# CH32V203CCT-R0.net
KiCad netlist of a schematic drawn in Altium Designer
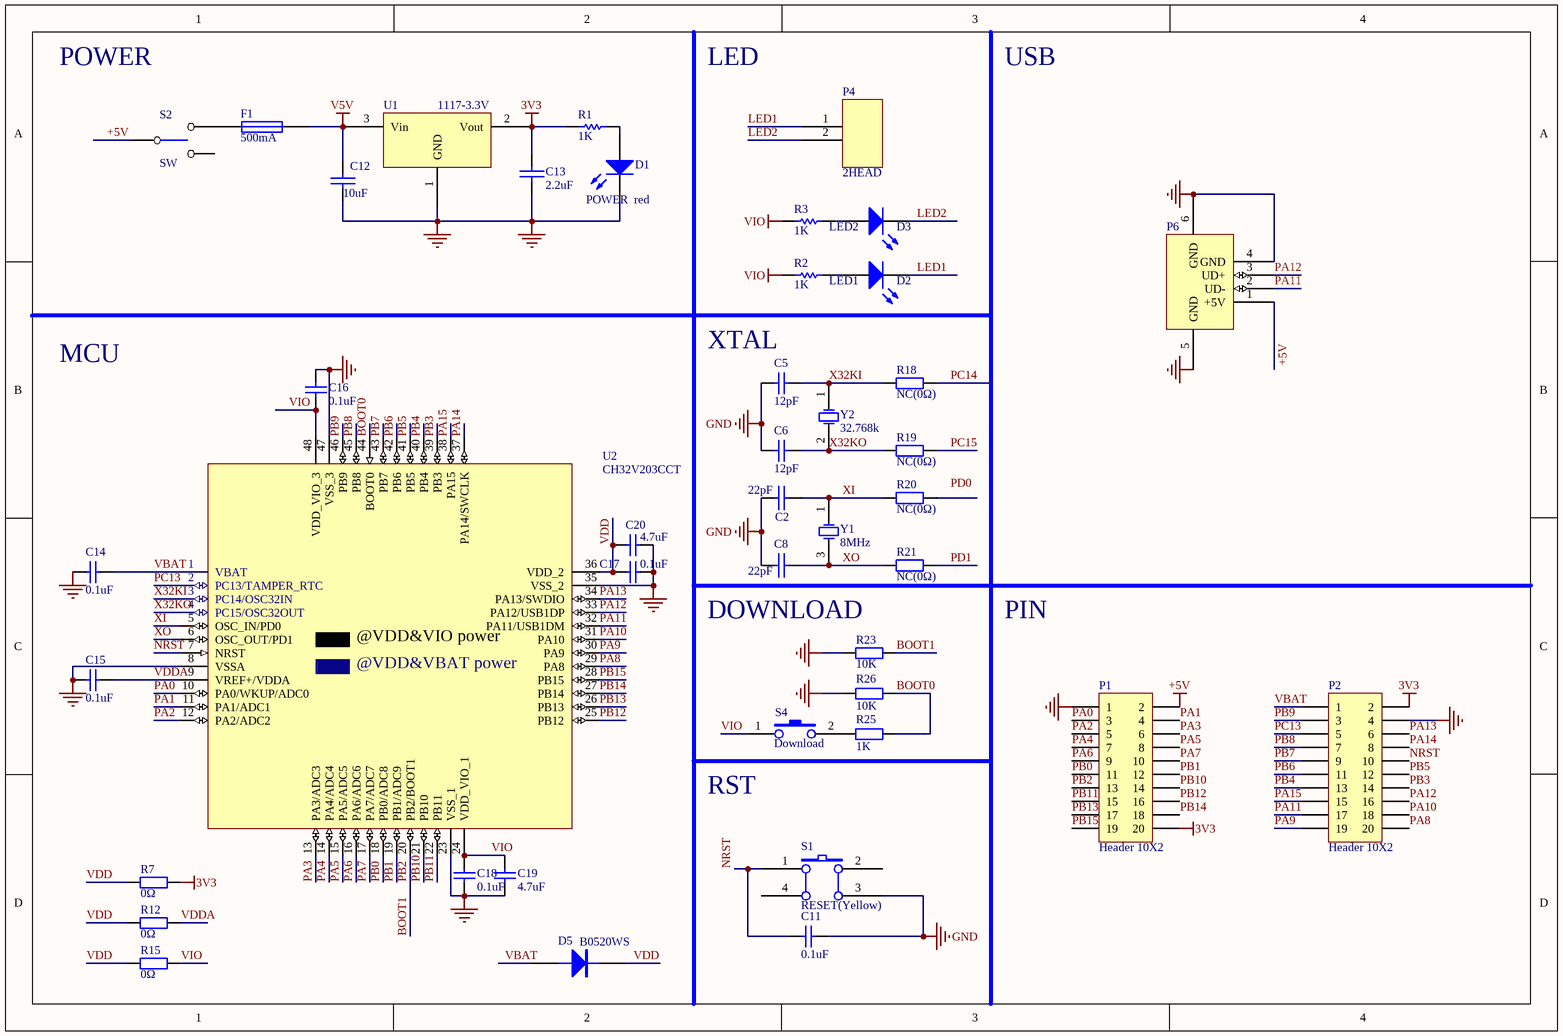
[diagram p0: CH32V203CCT-R0.SchDoc]

(export (version "E")
  (design (tool "Eeschema 10.0.6"))
  (components
    (comp (ref "C2")
      (value "22pF")
      (footprint "0603_C")
      (description "Capacitor")
      (libsource (lib "*") (part "CAP"))
    )
    (comp (ref "C5")
      (value "12pF")
      (footprint "0603_C")
      (description "Capacitor")
      (libsource (lib "Miscellaneous Devices") (part "Cap"))
    )
    (comp (ref "C6")
      (value "12pF")
      (footprint "0603_C")
      (description "Capacitor")
      (libsource (lib "Miscellaneous Devices") (part "Cap"))
    )
    (comp (ref "C8")
      (value "22pF")
      (footprint "0603_C")
      (description "Capacitor")
      (libsource (lib "*") (part "CAP"))
    )
    (comp (ref "C11")
      (value "0.1uF")
      (footprint "0603_C")
      (description "Capacitor")
      (libsource (lib "Miscellaneous Devices") (part "Cap"))
    )
    (comp (ref "C12")
      (value "10uF")
      (footprint "3216_C")
      (description "Capacitor")
      (libsource (lib "*") (part "CAP"))
    )
    (comp (ref "C13")
      (value "2.2uF")
      (footprint "0603_C")
      (description "Capacitor")
      (libsource (lib "*") (part "CAP"))
    )
    (comp (ref "C14")
      (value "0.1uF")
      (footprint "0603_C")
      (description "Capacitor")
      (fields (field (name "PUBLISHER") "Altium Limited"))
      (libsource (lib "*") (part "Cap"))
    )
    (comp (ref "C15")
      (value "0.1uF")
      (footprint "0603_C")
      (description "Capacitor")
      (fields (field (name "PUBLISHER") "Altium Limited"))
      (libsource (lib "*") (part "Cap"))
    )
    (comp (ref "C16")
      (value "0.1uF")
      (footprint "0603_C")
      (description "Capacitor")
      (fields (field (name "PUBLISHER") "Altium Limited"))
      (libsource (lib "*") (part "Cap"))
    )
    (comp (ref "C17")
      (value "0.1uF")
      (footprint "0603_C")
      (description "Capacitor")
      (fields (field (name "PUBLISHER") "Altium Limited"))
      (libsource (lib "*") (part "Cap"))
    )
    (comp (ref "C18")
      (value "0.1uF")
      (footprint "0603_C")
      (description "Capacitor")
      (fields (field (name "PUBLISHER") "Altium Limited"))
      (libsource (lib "*") (part "Cap"))
    )
    (comp (ref "C19")
      (value "4.7uF")
      (footprint "0603_C")
      (description "Capacitor")
      (fields (field (name "PUBLISHER") "Altium Limited"))
      (libsource (lib "*") (part "Cap"))
    )
    (comp (ref "C20")
      (value "4.7uF")
      (footprint "0603_C")
      (description "Capacitor")
      (fields (field (name "PUBLISHER") "Altium Limited"))
      (libsource (lib "*") (part "Cap"))
    )
    (comp (ref "D1")
      (value "POWER  red")
      (footprint "0603+")
      (description "Typical INFRARED GaAs LED")
      (fields (field (name "PUBLISHER") "Altium Limited"))
      (libsource (lib "*") (part "LED0"))
    )
    (comp (ref "D2")
      (value "LED1")
      (footprint "0603+")
      (description "Typical INFRARED GaAs LED")
      (fields (field (name "PUBLISHER") "Altium Limited"))
      (libsource (lib "*") (part "LED0"))
    )
    (comp (ref "D3")
      (value "LED2")
      (footprint "0603+")
      (description "Typical INFRARED GaAs LED")
      (fields (field (name "PUBLISHER") "Altium Limited"))
      (libsource (lib "*") (part "LED0"))
    )
    (comp (ref "D5")
      (value "B0520WS")
      (footprint "SOD-323")
      (description "Diode")
      (libsource (lib "*") (part "DIODE"))
    )
    (comp (ref "F1")
      (value "500mA")
      (footprint "0603")
      (description "Fuse")
      (libsource (lib "*") (part "FUSE1"))
    )
    (comp (ref "P1")
      (value "Header 10X2")
      (footprint "IDC20-2.54mm")
      (description "Header, 10-Pin, Dual row")
      (fields (field (name "PUBLISHER") "Altium Limited"))
      (libsource (lib "*") (part "Header 10X2"))
    )
    (comp (ref "P2")
      (value "Header 10X2")
      (footprint "IDC20-2.54mm")
      (description "Header, 10-Pin, Dual row")
      (fields (field (name "PUBLISHER") "Altium Limited"))
      (libsource (lib "*") (part "Header 10X2"))
    )
    (comp (ref "P4") (value "2HEAD") (footprint "SIP2-2.54mm") (libsource (lib "*") (part "2HEAD")))
    (comp (ref "P6")
      (value "USB_A")
      (footprint "USBAF")
      (description "USB Port")
      (libsource (lib "*") (part "USB"))
    )
    (comp (ref "R1")
      (value "1K")
      (footprint "0603")
      (description "Semiconductor Resistor")
      (fields (field (name "PUBLISHER") "Altium Limited"))
      (libsource (lib "*") (part "Res Semi"))
    )
    (comp (ref "R2")
      (value "1K")
      (footprint "0603")
      (description "Semiconductor Resistor")
      (fields (field (name "PUBLISHER") "Altium Limited"))
      (libsource (lib "*") (part "Res Semi"))
    )
    (comp (ref "R3")
      (value "1K")
      (footprint "0603")
      (description "Semiconductor Resistor")
      (fields (field (name "PUBLISHER") "Altium Limited"))
      (libsource (lib "*") (part "Res Semi"))
    )
    (comp (ref "R7")
      (value "0Ω")
      (footprint "0603")
      (description "Resistor")
      (libsource (lib "Miscellaneous Devices") (part "Res2"))
    )
    (comp (ref "R12")
      (value "0Ω")
      (footprint "0603")
      (description "Resistor")
      (libsource (lib "Miscellaneous Devices") (part "Res2"))
    )
    (comp (ref "R15")
      (value "0Ω")
      (footprint "0603")
      (description "Resistor")
      (libsource (lib "Miscellaneous Devices") (part "Res2"))
    )
    (comp (ref "R18")
      (value "NC(0Ω)")
      (footprint "0603")
      (description "Resistor")
      (libsource (lib "") (part "Res2_1"))
    )
    (comp (ref "R19")
      (value "NC(0Ω)")
      (footprint "0603")
      (description "Resistor")
      (libsource (lib "Miscellaneous Devices") (part "Res2"))
    )
    (comp (ref "R20")
      (value "NC(0Ω)")
      (footprint "0603")
      (description "Resistor")
      (libsource (lib "Miscellaneous Devices") (part "Res2"))
    )
    (comp (ref "R21")
      (value "NC(0Ω)")
      (footprint "0603")
      (description "Resistor")
      (libsource (lib "Miscellaneous Devices") (part "Res2"))
    )
    (comp (ref "R23")
      (value "10K")
      (footprint "CHXXX:0603")
      (description "Resistor")
      (fields (field (name "PUBLISHER") "Altium Limited"))
      (libsource (lib "Miscellaneous Devices") (part "Res2"))
    )
    (comp (ref "R25")
      (value "1K")
      (footprint "CHXXX:0603")
      (description "Resistor")
      (fields (field (name "PUBLISHER") "Altium Limited"))
      (libsource (lib "Miscellaneous Devices") (part "Res2"))
    )
    (comp (ref "R26")
      (value "10K")
      (footprint "CHXXX:0603")
      (description "Resistor")
      (fields (field (name "PUBLISHER") "Altium Limited"))
      (libsource (lib "Miscellaneous Devices") (part "Res2"))
    )
    (comp (ref "S1")
      (value "RESET(Yellow)")
      (footprint "KEYX")
      (description "SE PUSHBUTTON")
      (libsource (lib "Documents") (part "SW PUSHBUTTON"))
    )
    (comp (ref "S2") (value "SW") (footprint "KEY2") (libsource (lib "*") (part "SW")))
    (comp (ref "S4")
      (value "Download")
      (footprint "SMD_6.1x3.65x2.5mm-KEY")
      (libsource (lib "wch_sch_others") (part "KEY1"))
    )
    (comp (ref "U1")
      (value "1117-3.3V")
      (footprint "SOT-23")
      (libsource (lib "wch_sch_others") (part "6219P33M"))
    )
    (comp (ref "U2")
      (value "CH32V203CCT")
      (footprint "LQFP48")
      (description "RISC-V MCU, 192MHz, USB FS, PIOC, ADC, TKEY, 2*OPA, 2*CMP")
      (libsource (lib "CHXXX") (part "CH32V203CCT"))
    )
    (comp (ref "Y1")
      (value "8MHz")
      (footprint "XT3225")
      (description "Crystal Oscillator")
      (fields (field (name "PUBLISHER") "Altium Limited"))
      (libsource (lib "*") (part "XTAL"))
    )
    (comp (ref "Y2")
      (value "32.768k")
      (footprint "FC-135")
      (description "Crystal Oscillator")
      (fields (field (name "PUBLISHER") "Altium Limited"))
      (libsource (lib "Miscellaneous Devices") (part "XTAL"))
    )
  )
  (nets
    (net (code "1") (name "+5V") (class "Default")
      (node (ref "P1") (pin "2") (pinfunction "2_2") (pintype "passive"))
      (node (ref "P6") (pin "1") (pinfunction "+5V_1") (pintype "power_in"))
      (node (ref "S2") (pin "1") (pinfunction "1_1") (pintype "passive"))
    )
    (net (code "3") (name "/BOOT0") (class "Default")
      (node (ref "R25") (pin "1") (pinfunction "1_1") (pintype "passive"))
      (node (ref "R26") (pin "1") (pinfunction "1_1") (pintype "passive"))
      (node (ref "U2") (pin "44") (pinfunction "BOOT0_44") (pintype "input"))
    )
    (net (code "4") (name "/BOOT1") (class "Default")
      (node (ref "P1") (pin "13") (pinfunction "13_13") (pintype "passive"))
      (node (ref "R23") (pin "1") (pinfunction "1_1") (pintype "passive"))
      (node (ref "U2") (pin "20") (pinfunction "PB2/BOOT1_20") (pintype "bidirectional"))
    )
    (net (code "5") (name "/LED1") (class "Default")
      (node (ref "D2") (pin "2") (pinfunction "K_2") (pintype "passive"))
      (node (ref "P4") (pin "1") (pintype "passive"))
    )
    (net (code "6") (name "/LED2") (class "Default")
      (node (ref "D3") (pin "2") (pinfunction "K_2") (pintype "passive"))
      (node (ref "P4") (pin "2") (pintype "passive"))
    )
    (net (code "7") (name "/NRST") (class "Default")
      (node (ref "C11") (pin "2") (pinfunction "2_2") (pintype "passive"))
      (node (ref "P2") (pin "10") (pinfunction "10_10") (pintype "passive"))
      (node (ref "S1") (pin "1") (pinfunction "A0_1") (pintype "passive"))
      (node (ref "U2") (pin "7") (pinfunction "NRST_7") (pintype "input"))
    )
    (net (code "8") (name "/PA0") (class "Default")
      (node (ref "P1") (pin "3") (pinfunction "3_3") (pintype "passive"))
      (node (ref "U2") (pin "10") (pinfunction "PA0/WKUP/ADC0_10") (pintype "bidirectional"))
    )
    (net (code "9") (name "/PA1") (class "Default")
      (node (ref "P1") (pin "4") (pinfunction "4_4") (pintype "passive"))
      (node (ref "U2") (pin "11") (pinfunction "PA1/ADC1_11") (pintype "bidirectional"))
    )
    (net (code "10") (name "/PA2") (class "Default")
      (node (ref "P1") (pin "5") (pinfunction "5_5") (pintype "passive"))
      (node (ref "U2") (pin "12") (pinfunction "PA2/ADC2_12") (pintype "bidirectional"))
    )
    (net (code "11") (name "/PA3") (class "Default")
      (node (ref "P1") (pin "6") (pinfunction "6_6") (pintype "passive"))
      (node (ref "U2") (pin "13") (pinfunction "PA3/ADC3_13") (pintype "bidirectional"))
    )
    (net (code "12") (name "/PA4") (class "Default")
      (node (ref "P1") (pin "7") (pinfunction "7_7") (pintype "passive"))
      (node (ref "U2") (pin "14") (pinfunction "PA4/ADC4_14") (pintype "bidirectional"))
    )
    (net (code "13") (name "/PA5") (class "Default")
      (node (ref "P1") (pin "8") (pinfunction "8_8") (pintype "passive"))
      (node (ref "U2") (pin "15") (pinfunction "PA5/ADC5_15") (pintype "bidirectional"))
    )
    (net (code "14") (name "/PA6") (class "Default")
      (node (ref "P1") (pin "9") (pinfunction "9_9") (pintype "passive"))
      (node (ref "U2") (pin "16") (pinfunction "PA6/ADC6_16") (pintype "bidirectional"))
    )
    (net (code "15") (name "/PA7") (class "Default")
      (node (ref "P1") (pin "10") (pinfunction "10_10") (pintype "passive"))
      (node (ref "U2") (pin "17") (pinfunction "PA7/ADC7_17") (pintype "bidirectional"))
    )
    (net (code "16") (name "/PA8") (class "Default")
      (node (ref "P2") (pin "20") (pinfunction "20_20") (pintype "passive"))
      (node (ref "U2") (pin "29") (pinfunction "PA8_29") (pintype "bidirectional"))
    )
    (net (code "17") (name "/PA9") (class "Default")
      (node (ref "P2") (pin "19") (pinfunction "19_19") (pintype "passive"))
      (node (ref "U2") (pin "30") (pinfunction "PA9_30") (pintype "bidirectional"))
    )
    (net (code "18") (name "/PA10") (class "Default")
      (node (ref "P2") (pin "18") (pinfunction "18_18") (pintype "passive"))
      (node (ref "U2") (pin "31") (pinfunction "PA10_31") (pintype "bidirectional"))
    )
    (net (code "19") (name "/PA11") (class "Default")
      (node (ref "P2") (pin "17") (pinfunction "17_17") (pintype "passive"))
      (node (ref "P6") (pin "2") (pinfunction "UD-_2") (pintype "bidirectional"))
      (node (ref "U2") (pin "32") (pinfunction "PA11/USB1DM_32") (pintype "bidirectional"))
    )
    (net (code "20") (name "/PA12") (class "Default")
      (node (ref "P2") (pin "16") (pinfunction "16_16") (pintype "passive"))
      (node (ref "P6") (pin "3") (pinfunction "UD+_3") (pintype "bidirectional"))
      (node (ref "U2") (pin "33") (pinfunction "PA12/USB1DP_33") (pintype "bidirectional"))
    )
    (net (code "21") (name "/PA13") (class "Default")
      (node (ref "P2") (pin "6") (pinfunction "6_6") (pintype "passive"))
      (node (ref "U2") (pin "34") (pinfunction "PA13/SWDIO_34") (pintype "bidirectional"))
    )
    (net (code "22") (name "/PA14") (class "Default")
      (node (ref "P2") (pin "8") (pinfunction "8_8") (pintype "passive"))
      (node (ref "U2") (pin "37") (pinfunction "PA14/SWCLK_37") (pintype "bidirectional"))
    )
    (net (code "23") (name "/PA15") (class "Default")
      (node (ref "P2") (pin "15") (pinfunction "15_15") (pintype "passive"))
      (node (ref "U2") (pin "38") (pinfunction "PA15_38") (pintype "bidirectional"))
    )
    (net (code "24") (name "/PB0") (class "Default")
      (node (ref "P1") (pin "11") (pinfunction "11_11") (pintype "passive"))
      (node (ref "U2") (pin "18") (pinfunction "PB0/ADC8_18") (pintype "bidirectional"))
    )
    (net (code "25") (name "/PB1") (class "Default")
      (node (ref "P1") (pin "12") (pinfunction "12_12") (pintype "passive"))
      (node (ref "U2") (pin "19") (pinfunction "PB1/ADC9_19") (pintype "bidirectional"))
    )
    (net (code "26") (name "/PB3") (class "Default")
      (node (ref "P2") (pin "14") (pinfunction "14_14") (pintype "passive"))
      (node (ref "U2") (pin "39") (pinfunction "PB3_39") (pintype "bidirectional"))
    )
    (net (code "27") (name "/PB4") (class "Default")
      (node (ref "P2") (pin "13") (pinfunction "13_13") (pintype "passive"))
      (node (ref "U2") (pin "40") (pinfunction "PB4_40") (pintype "bidirectional"))
    )
    (net (code "28") (name "/PB5") (class "Default")
      (node (ref "P2") (pin "12") (pinfunction "12_12") (pintype "passive"))
      (node (ref "U2") (pin "41") (pinfunction "PB5_41") (pintype "bidirectional"))
    )
    (net (code "29") (name "/PB6") (class "Default")
      (node (ref "P2") (pin "11") (pinfunction "11_11") (pintype "passive"))
      (node (ref "U2") (pin "42") (pinfunction "PB6_42") (pintype "bidirectional"))
    )
    (net (code "30") (name "/PB7") (class "Default")
      (node (ref "P2") (pin "9") (pinfunction "9_9") (pintype "passive"))
      (node (ref "U2") (pin "43") (pinfunction "PB7_43") (pintype "bidirectional"))
    )
    (net (code "31") (name "/PB8") (class "Default")
      (node (ref "P2") (pin "7") (pinfunction "7_7") (pintype "passive"))
      (node (ref "U2") (pin "45") (pinfunction "PB8_45") (pintype "bidirectional"))
    )
    (net (code "32") (name "/PB9") (class "Default")
      (node (ref "P2") (pin "3") (pinfunction "3_3") (pintype "passive"))
      (node (ref "U2") (pin "46") (pinfunction "PB9_46") (pintype "bidirectional"))
    )
    (net (code "33") (name "/PB10") (class "Default")
      (node (ref "P1") (pin "14") (pinfunction "14_14") (pintype "passive"))
      (node (ref "U2") (pin "21") (pinfunction "PB10_21") (pintype "bidirectional"))
    )
    (net (code "34") (name "/PB11") (class "Default")
      (node (ref "P1") (pin "15") (pinfunction "15_15") (pintype "passive"))
      (node (ref "U2") (pin "22") (pinfunction "PB11_22") (pintype "bidirectional"))
    )
    (net (code "35") (name "/PB12") (class "Default")
      (node (ref "P1") (pin "16") (pinfunction "16_16") (pintype "passive"))
      (node (ref "U2") (pin "25") (pinfunction "PB12_25") (pintype "bidirectional"))
    )
    (net (code "36") (name "/PB13") (class "Default")
      (node (ref "P1") (pin "17") (pinfunction "17_17") (pintype "passive"))
      (node (ref "U2") (pin "26") (pinfunction "PB13_26") (pintype "bidirectional"))
    )
    (net (code "37") (name "/PB14") (class "Default")
      (node (ref "P1") (pin "18") (pinfunction "18_18") (pintype "passive"))
      (node (ref "U2") (pin "27") (pinfunction "PB14_27") (pintype "bidirectional"))
    )
    (net (code "38") (name "/PB15") (class "Default")
      (node (ref "P1") (pin "19") (pinfunction "19_19") (pintype "passive"))
      (node (ref "U2") (pin "28") (pinfunction "PB15_28") (pintype "bidirectional"))
    )
    (net (code "39") (name "/PC13") (class "Default")
      (node (ref "P2") (pin "5") (pinfunction "5_5") (pintype "passive"))
      (node (ref "U2") (pin "2") (pinfunction "PC13/TAMPER_RTC_2") (pintype "bidirectional"))
    )
    (net (code "40") (name "/PC14") (class "Default")
      (node (ref "R18") (pin "2") (pinfunction "2_2") (pintype "passive"))
    )
    (net (code "41") (name "/PC15") (class "Default")
      (node (ref "R19") (pin "1") (pinfunction "1_1") (pintype "passive"))
    )
    (net (code "43") (name "/PD1") (class "Default")
      (node (ref "R21") (pin "1") (pinfunction "1_1") (pintype "passive"))
    )
    (net (code "44") (name "/VBAT") (class "Default")
      (node (ref "C14") (pin "1") (pinfunction "1_1") (pintype "passive"))
      (node (ref "D5") (pin "1") (pinfunction "A_1") (pintype "passive"))
      (node (ref "P2") (pin "1") (pinfunction "1_1") (pintype "passive"))
      (node (ref "U2") (pin "1") (pinfunction "VBAT_1") (pintype "power_in"))
    )
    (net (code "45") (name "/VDD") (class "Default")
      (node (ref "C17") (pin "2") (pinfunction "2_2") (pintype "passive"))
      (node (ref "C20") (pin "2") (pinfunction "2_2") (pintype "passive"))
      (node (ref "D5") (pin "2") (pinfunction "K_2") (pintype "passive"))
      (node (ref "R12") (pin "2") (pinfunction "2_2") (pintype "passive"))
      (node (ref "R15") (pin "2") (pinfunction "2_2") (pintype "passive"))
      (node (ref "R7") (pin "2") (pinfunction "2_2") (pintype "passive"))
      (node (ref "U2") (pin "36") (pinfunction "VDD_2_36") (pintype "power_in"))
    )
    (net (code "46") (name "/VDDA") (class "Default")
      (node (ref "C15") (pin "1") (pinfunction "1_1") (pintype "passive"))
      (node (ref "R12") (pin "1") (pinfunction "1_1") (pintype "passive"))
      (node (ref "U2") (pin "9") (pinfunction "VREF+/VDDA_9") (pintype "power_in"))
    )
    (net (code "47") (name "/X32KI") (class "Default")
      (node (ref "C5") (pin "1") (pinfunction "1_1") (pintype "passive"))
      (node (ref "R18") (pin "1") (pinfunction "1_1") (pintype "passive"))
      (node (ref "U2") (pin "3") (pinfunction "PC14/OSC32IN_3") (pintype "bidirectional"))
      (node (ref "Y2") (pin "1") (pinfunction "OSC1_1") (pintype "passive"))
    )
    (net (code "48") (name "/X32KO") (class "Default")
      (node (ref "C6") (pin "1") (pinfunction "1_1") (pintype "passive"))
      (node (ref "R19") (pin "2") (pinfunction "2_2") (pintype "passive"))
      (node (ref "U2") (pin "4") (pinfunction "PC15/OSC32OUT_4") (pintype "bidirectional"))
      (node (ref "Y2") (pin "2") (pinfunction "OSC2_2") (pintype "passive"))
    )
    (net (code "49") (name "/XI") (class "Default")
      (node (ref "C2") (pin "2") (pinfunction "2_2") (pintype "passive"))
      (node (ref "R20") (pin "2") (pinfunction "2_2") (pintype "passive"))
      (node (ref "U2") (pin "5") (pinfunction "OSC_IN/PD0_5") (pintype "bidirectional"))
      (node (ref "Y1") (pin "1") (pinfunction "OSC1_1") (pintype "passive"))
    )
    (net (code "50") (name "/XO") (class "Default")
      (node (ref "C8") (pin "2") (pinfunction "2_2") (pintype "passive"))
      (node (ref "R21") (pin "2") (pinfunction "2_2") (pintype "passive"))
      (node (ref "U2") (pin "6") (pinfunction "OSC_OUT/PD1_6") (pintype "bidirectional"))
      (node (ref "Y1") (pin "3") (pinfunction "OSC2_3") (pintype "passive"))
    )
    (net (code "51") (name "3V3") (class "Default")
      (node (ref "C13") (pin "1") (pinfunction "1_1") (pintype "passive"))
      (node (ref "P1") (pin "20") (pinfunction "20_20") (pintype "passive"))
      (node (ref "P2") (pin "2") (pinfunction "2_2") (pintype "passive"))
      (node (ref "R1") (pin "2") (pinfunction "2_2") (pintype "passive"))
      (node (ref "R7") (pin "1") (pinfunction "1_1") (pintype "passive"))
      (node (ref "U1") (pin "2") (pinfunction "Vout_2") (pintype "passive"))
    )
    (net (code "52") (name "GND") (class "Default")
      (node (ref "C11") (pin "1") (pinfunction "1_1") (pintype "passive"))
      (node (ref "C12") (pin "2") (pinfunction "2_2") (pintype "passive"))
      (node (ref "C13") (pin "2") (pinfunction "2_2") (pintype "passive"))
      (node (ref "C14") (pin "2") (pinfunction "2_2") (pintype "passive"))
      (node (ref "C15") (pin "2") (pinfunction "2_2") (pintype "passive"))
      (node (ref "C16") (pin "1") (pinfunction "1_1") (pintype "passive"))
      (node (ref "C17") (pin "1") (pinfunction "1_1") (pintype "passive"))
      (node (ref "C18") (pin "1") (pinfunction "1_1") (pintype "passive"))
      (node (ref "C19") (pin "2") (pinfunction "2_2") (pintype "passive"))
      (node (ref "C2") (pin "1") (pinfunction "1_1") (pintype "passive"))
      (node (ref "C20") (pin "1") (pinfunction "1_1") (pintype "passive"))
      (node (ref "C5") (pin "2") (pinfunction "2_2") (pintype "passive"))
      (node (ref "C6") (pin "2") (pinfunction "2_2") (pintype "passive"))
      (node (ref "C8") (pin "1") (pinfunction "1_1") (pintype "passive"))
      (node (ref "D1") (pin "2") (pinfunction "K_2") (pintype "passive"))
      (node (ref "P1") (pin "1") (pinfunction "1_1") (pintype "passive"))
      (node (ref "P2") (pin "4") (pinfunction "4_4") (pintype "passive"))
      (node (ref "P6") (pin "4") (pinfunction "GND_4") (pintype "power_in"))
      (node (ref "P6") (pin "5") (pinfunction "GND_5") (pintype "power_in"))
      (node (ref "P6") (pin "6") (pinfunction "GND_6") (pintype "power_in"))
      (node (ref "R23") (pin "2") (pinfunction "2_2") (pintype "passive"))
      (node (ref "R26") (pin "2") (pinfunction "2_2") (pintype "passive"))
      (node (ref "S1") (pin "3") (pinfunction "B1_3") (pintype "passive"))
      (node (ref "U1") (pin "1") (pinfunction "GND_1") (pintype "passive"))
      (node (ref "U2") (pin "23") (pinfunction "VSS_1_23") (pintype "power_in"))
      (node (ref "U2") (pin "35") (pinfunction "VSS_2_35") (pintype "power_in"))
      (node (ref "U2") (pin "47") (pinfunction "VSS_3_47") (pintype "power_in"))
      (node (ref "U2") (pin "8") (pinfunction "VSSA_8") (pintype "power_in"))
    )
    (net (code "53") (name "Net-(D1-A)") (class "Default")
      (node (ref "D1") (pin "1") (pinfunction "A_1") (pintype "passive"))
      (node (ref "R1") (pin "1") (pinfunction "1_1") (pintype "passive"))
    )
    (net (code "54") (name "Net-(D2-A)") (class "Default")
      (node (ref "D2") (pin "1") (pinfunction "A_1") (pintype "passive"))
      (node (ref "R2") (pin "2") (pinfunction "2_2") (pintype "passive"))
    )
    (net (code "55") (name "Net-(D3-A)") (class "Default")
      (node (ref "D3") (pin "1") (pinfunction "A_1") (pintype "passive"))
      (node (ref "R3") (pin "2") (pinfunction "2_2") (pintype "passive"))
    )
    (net (code "56") (name "Net-(F1-Pad1)") (class "Default")
      (node (ref "F1") (pin "1") (pinfunction "1_1") (pintype "passive"))
      (node (ref "S2") (pin "3") (pinfunction "3_3") (pintype "passive"))
    )
    (net (code "57") (name "Net-(R25-Pad2)") (class "Default")
      (node (ref "R25") (pin "2") (pinfunction "2_2") (pintype "passive"))
      (node (ref "S4") (pin "2") (pinfunction "2_2") (pintype "passive"))
    )
    (net (code "58") (name "V5V") (class "Default")
      (node (ref "C12") (pin "1") (pinfunction "1_1") (pintype "passive"))
      (node (ref "F1") (pin "2") (pinfunction "2_2") (pintype "passive"))
      (node (ref "U1") (pin "3") (pinfunction "Vin_3") (pintype "passive"))
    )
    (net (code "59") (name "VIO") (class "Default")
      (node (ref "C16") (pin "2") (pinfunction "2_2") (pintype "passive"))
      (node (ref "C18") (pin "2") (pinfunction "2_2") (pintype "passive"))
      (node (ref "C19") (pin "1") (pinfunction "1_1") (pintype "passive"))
      (node (ref "R15") (pin "1") (pinfunction "1_1") (pintype "passive"))
      (node (ref "R2") (pin "1") (pinfunction "1_1") (pintype "passive"))
      (node (ref "R3") (pin "1") (pinfunction "1_1") (pintype "passive"))
      (node (ref "S4") (pin "1") (pinfunction "1_1") (pintype "passive"))
      (node (ref "U2") (pin "24") (pinfunction "VDD_VIO_1_24") (pintype "power_in"))
      (node (ref "U2") (pin "48") (pinfunction "VDD_VIO_3_48") (pintype "power_in"))
    )
    (net (code "60") (name "unconnected-(R20-Pad1)") (class "Default")
      (node (ref "R20") (pin "1") (pinfunction "1_1") (pintype "passive"))
    )
    (net (code "61") (name "unconnected-(S1-A1-Pad4)") (class "Default")
      (node (ref "S1") (pin "4") (pinfunction "A1_4") (pintype "passive"))
    )
    (net (code "62") (name "unconnected-(S1-B0-Pad2)") (class "Default")
      (node (ref "S1") (pin "2") (pinfunction "B0_2") (pintype "passive"))
    )
    (net (code "63") (name "unconnected-(S2-Pad2)") (class "Default")
      (node (ref "S2") (pin "2") (pinfunction "2_2") (pintype "passive"))
    )
  )
)
